# ESPTempMonitorSch.net
KiCad netlist of a schematic drawn in Altium Designer
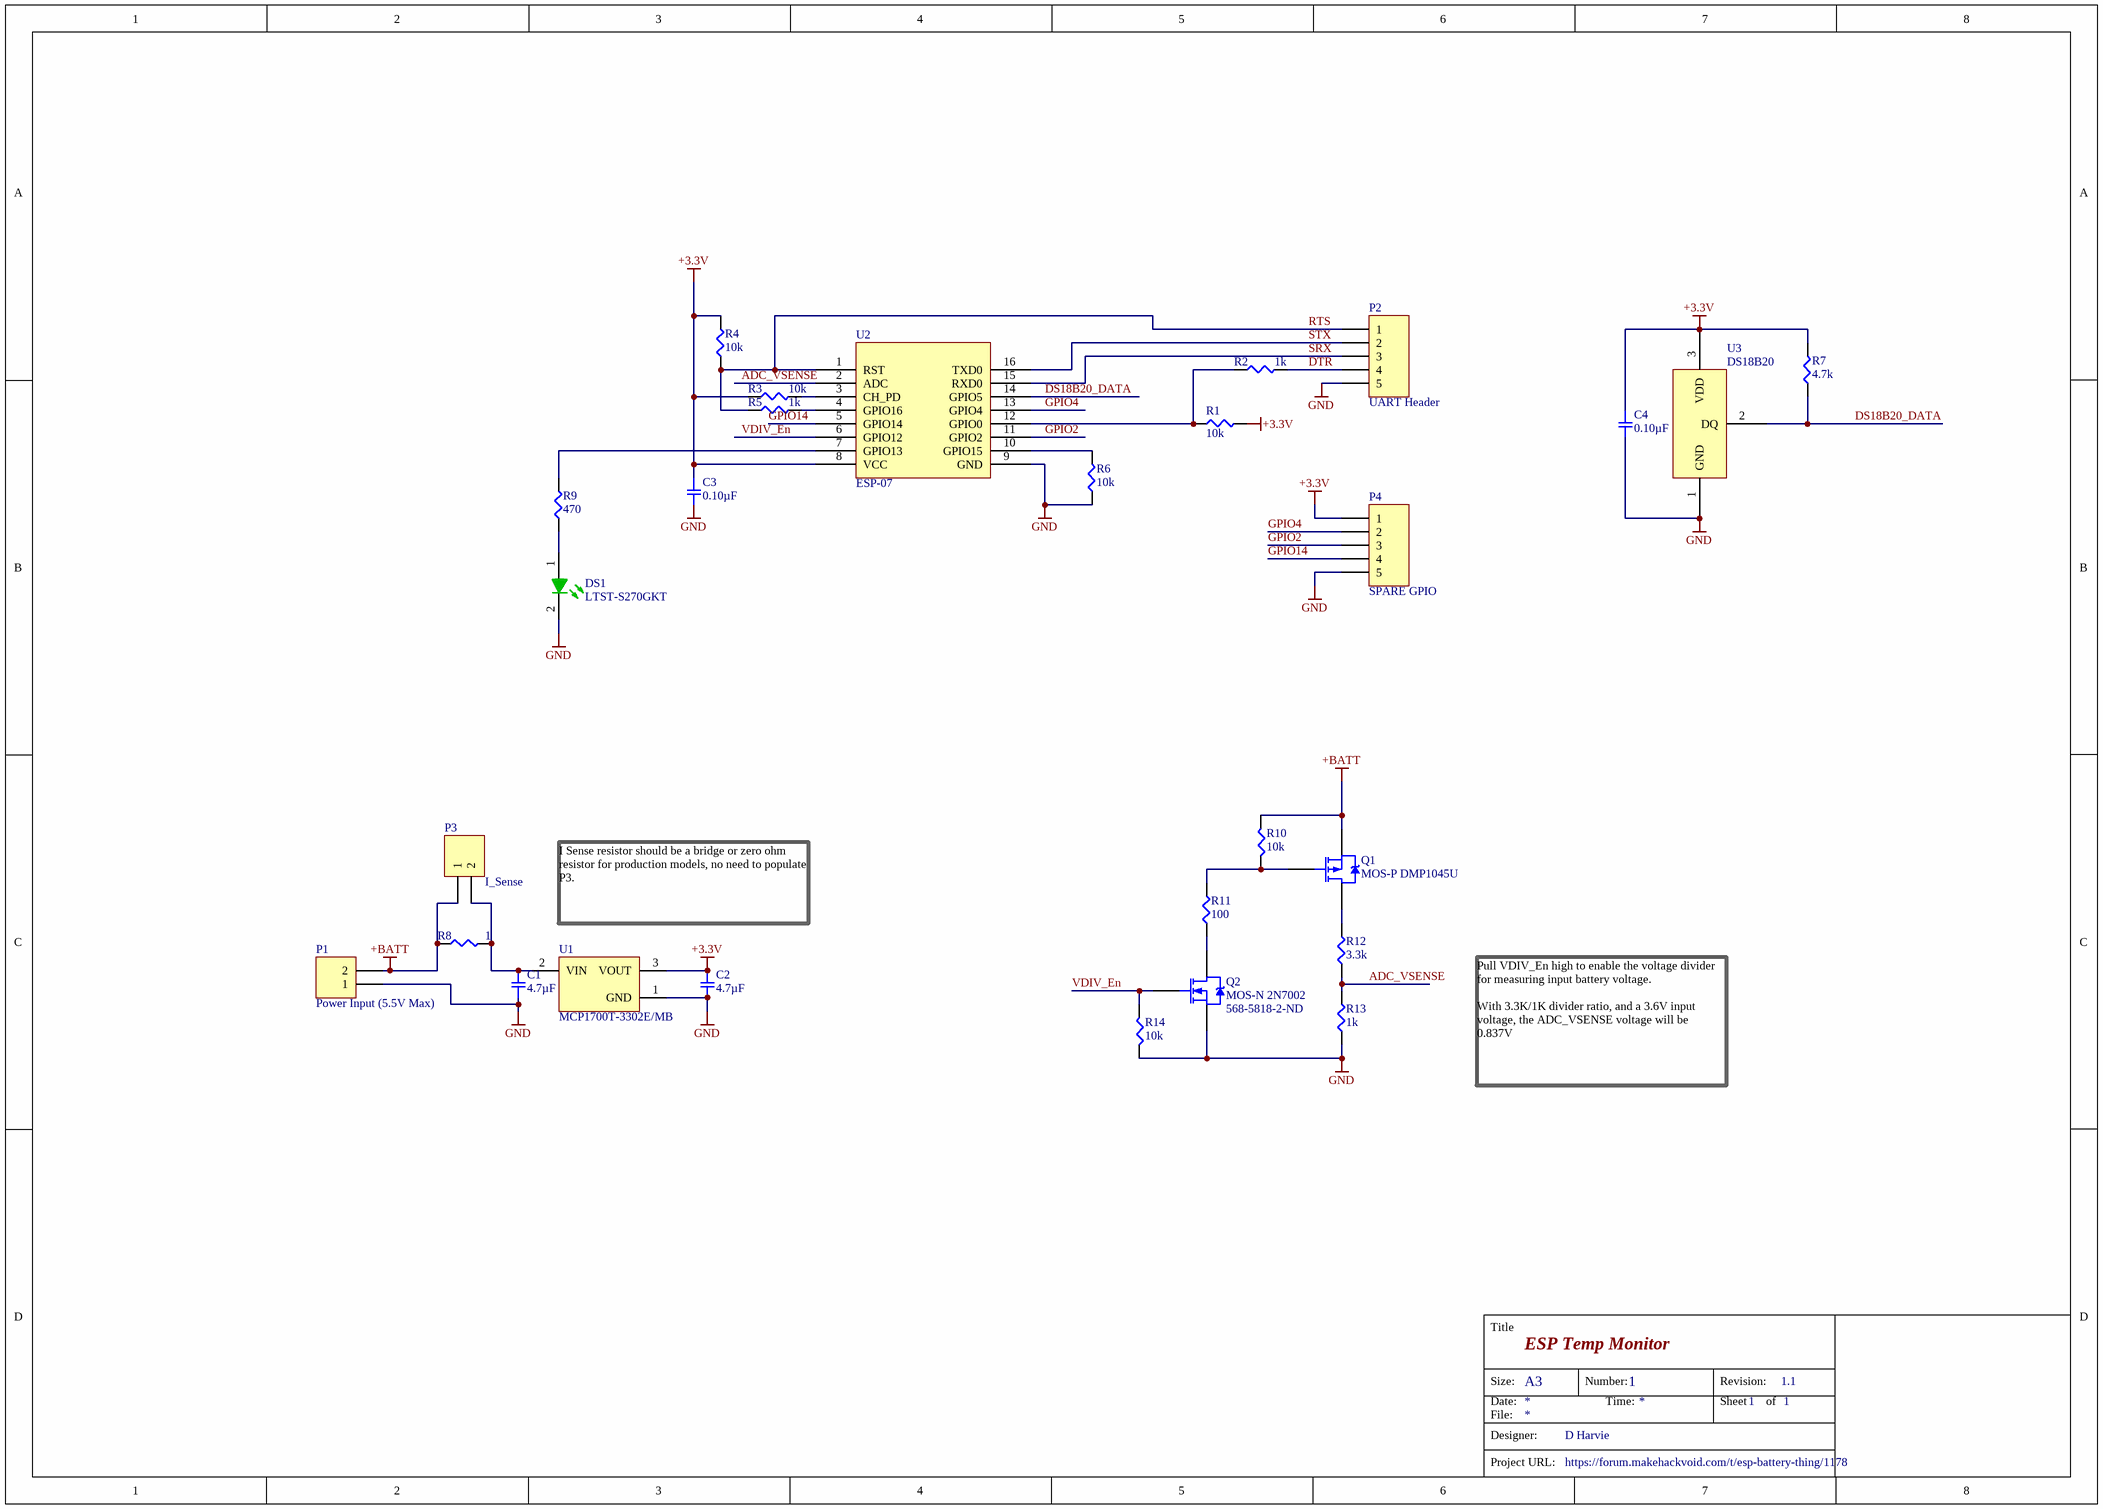
[diagram p0: ESPTempMonitorSch.SchDoc]

(export (version "E")
  (design (tool "Eeschema 10.0.6"))
  (components
    (comp (ref "C1")
      (value "4.7µF")
      (footprint "SMD-0805C")
      (description "CAP CER 4.7UF 16V X7R 0805")
      (fields
        (field (name "DIGI-KEY PART NUMBER") "490-10557-1-ND")
        (field (name "PART NUMBER") "GCJ21BR71C475KA01L")
      )
      (libsource (lib "capacitor_murata_0805") (part "GCJ21BR71C475KA01L"))
    )
    (comp (ref "C2")
      (value "4.7µF")
      (footprint "SMD-0805C")
      (description "CAP CER 4.7UF 16V X7R 0805")
      (fields
        (field (name "DIGI-KEY PART NUMBER") "490-10557-1-ND")
        (field (name "PART NUMBER") "GCJ21BR71C475KA01L")
      )
      (libsource (lib "capacitor_murata_0805") (part "GCJ21BR71C475KA01L"))
    )
    (comp (ref "C3")
      (value "0.10µF")
      (footprint "SMD-0603C")
      (description "CAP CER 0.1UF 16V X7R 0603")
      (fields
        (field (name "DIGI-KEY PART NUMBER") "490-5796-1-ND")
        (field (name "PART NUMBER") "GCJ188R71C104KA01D")
      )
      (libsource (lib "capacitor_murata_0603") (part "GCJ188R71C104KA01D"))
    )
    (comp (ref "C4")
      (value "0.10µF")
      (footprint "SMD-0603C")
      (description "CAP CER 0.1UF 16V X7R 0603")
      (fields
        (field (name "DIGI-KEY PART NUMBER") "490-5796-1-ND")
        (field (name "PART NUMBER") "GCJ188R71C104KA01D")
      )
      (libsource (lib "capacitor_murata_0603") (part "GCJ188R71C104KA01D"))
    )
    (comp (ref "DS1")
      (value "LTST-S270GKT")
      (footprint "KING-0603LED_GREEN_V")
      (description "Green 569nm LED Indication - Discrete 2.1V 0603")
      (libsource (lib "RepositLib") (part "SMD - LED - Discrete - 0603 - Green"))
    )
    (comp (ref "P1")
      (value "Power Input (5.5V Max)")
      (footprint "HDR1X2")
      (description "Power Input")
      (fields (field (name "PUBLISHER") "Altium Limited"))
      (libsource (lib "") (part "Header 2_1"))
    )
    (comp (ref "P2")
      (value "UART Header")
      (footprint "HDR1X5")
      (description "Header, 5-Pin")
      (fields (field (name "PUBLISHER") "Altium Limited"))
      (libsource (lib "Miscellaneous Connectors") (part "Header 5"))
    )
    (comp (ref "P3")
      (value "I_Sense")
      (footprint "HDR1X2")
      (description "Power Input")
      (fields (field (name "PUBLISHER") "Altium Limited"))
      (libsource (lib "Miscellaneous Connectors") (part "Header 2"))
    )
    (comp (ref "P4")
      (value "SPARE GPIO")
      (footprint "HDR1X5")
      (description "Header, 5-Pin")
      (fields (field (name "PUBLISHER") "Altium Limited"))
      (libsource (lib "Miscellaneous Connectors") (part "Header 5"))
    )
    (comp (ref "Q1")
      (value "MOS-P DMP1045U")
      (footprint "SOT-23B_N")
      (description "PMOS-DMP1045U")
      (fields (field (name "PUBLISHER") "Altium Limited"))
      (libsource (lib "MainLib") (part "MOS-P DMP1045U"))
    )
    (comp (ref "Q2")
      (value "MOS-N 2N7002")
      (footprint "SOT-23B_N")
      (description "N-MOSFET 2N7002 NXP")
      (fields
        (field (name "SUPPLIER PART NUMBER 1") "568-5818-2-ND")
        (field (name "PUBLISHER") "Altium Limited")
      )
      (libsource (lib "MainLib") (part "MOS-N 2N7002"))
    )
    (comp (ref "R1")
      (value "10k")
      (footprint "SMD-0603-RES")
      (description "RES SMD 10K OHM 5% 1/10W 0603")
      (fields (field (name "PART NUMBER") "ERJ-3GEYJ103V") (field (name "DIGI-KEY PART NUMBER") "P10KGCT-ND"))
      (libsource (lib "Panasonic_ERJ_0603") (part "ERJ-3GEYJ103V"))
    )
    (comp (ref "R2")
      (value "1k")
      (footprint "SMD-0603-RES")
      (description "RES SMD 1K OHM 1% 1/10W 0603")
      (fields
        (field (name "PART NUMBER") "ERJ-3EKF1001V")
        (field (name "DIGI-KEY PART NUMBER") "P1.00KHCT-ND")
      )
      (libsource (lib "Panasonic_ERJ_0603") (part "ERJ-3EKF1001V"))
    )
    (comp (ref "R3")
      (value "10k")
      (footprint "SMD-0603-RES")
      (description "RES SMD 10K OHM 5% 1/10W 0603")
      (fields (field (name "PART NUMBER") "ERJ-3GEYJ103V") (field (name "DIGI-KEY PART NUMBER") "P10KGCT-ND"))
      (libsource (lib "Panasonic_ERJ_0603") (part "ERJ-3GEYJ103V"))
    )
    (comp (ref "R4")
      (value "10k")
      (footprint "SMD-0603-RES")
      (description "RES SMD 10K OHM 5% 1/10W 0603")
      (fields (field (name "PART NUMBER") "ERJ-3GEYJ103V") (field (name "DIGI-KEY PART NUMBER") "P10KGCT-ND"))
      (libsource (lib "Panasonic_ERJ_0603") (part "ERJ-3GEYJ103V"))
    )
    (comp (ref "R5")
      (value "1k")
      (footprint "SMD-0603-RES")
      (description "RES SMD 1K OHM 1% 1/10W 0603")
      (fields
        (field (name "PART NUMBER") "ERJ-3EKF1001V")
        (field (name "DIGI-KEY PART NUMBER") "P1.00KHCT-ND")
      )
      (libsource (lib "Panasonic_ERJ_0603") (part "ERJ-3EKF1001V"))
    )
    (comp (ref "R6")
      (value "10k")
      (footprint "SMD-0603-RES")
      (description "RES SMD 10K OHM 5% 1/10W 0603")
      (fields (field (name "PART NUMBER") "ERJ-3GEYJ103V") (field (name "DIGI-KEY PART NUMBER") "P10KGCT-ND"))
      (libsource (lib "Panasonic_ERJ_0603") (part "ERJ-3GEYJ103V"))
    )
    (comp (ref "R7")
      (value "4.7k")
      (footprint "SMD-0603-RES")
      (description "RES SMD 4.7K OHM 5% 1/10W 0603")
      (fields
        (field (name "PART NUMBER") "ERJ-3GEYJ472V")
        (field (name "DIGI-KEY PART NUMBER") "P4.7KGCT-ND")
      )
      (libsource (lib "Panasonic_ERJ_0603") (part "ERJ-3GEYJ472V"))
    )
    (comp (ref "R8")
      (value "1")
      (footprint "SMD-0603-RES")
      (description "RES SMD 1 OHM 1% 1/4W 0603")
      (fields (field (name "PART NUMBER") "ERJ-3BQF1R0V") (field (name "DIGI-KEY PART NUMBER") "P17371CT-ND"))
      (libsource (lib "Panasonic_ERJ_0603") (part "ERJ-3BQF1R0V"))
    )
    (comp (ref "R9")
      (value "470")
      (footprint "SMD-0603-RES")
      (description "RES SMD 470 OHM 5% 1/10W 0603")
      (fields (field (name "PART NUMBER") "ERJ-3GEYJ471V") (field (name "DIGI-KEY PART NUMBER") "P470GCT-ND"))
      (libsource (lib "Panasonic_ERJ_0603") (part "ERJ-3GEYJ471V"))
    )
    (comp (ref "R10")
      (value "10k")
      (footprint "SMD-0603-RES")
      (description "RES SMD 10K OHM 5% 1/10W 0603")
      (fields (field (name "PART NUMBER") "ERJ-3GEYJ103V") (field (name "DIGI-KEY PART NUMBER") "P10KGCT-ND"))
      (libsource (lib "Panasonic_ERJ_0603") (part "ERJ-3GEYJ103V"))
    )
    (comp (ref "R11")
      (value "100")
      (footprint "SMD-0603-RES")
      (description "RES SMD 100 OHM 1% 1/10W 0603")
      (fields (field (name "PART NUMBER") "ERJ-3EKF1000V") (field (name "DIGI-KEY PART NUMBER") "P100HCT-ND"))
      (libsource (lib "Panasonic_ERJ_0603") (part "ERJ-3EKF1000V"))
    )
    (comp (ref "R12")
      (value "3.3k")
      (footprint "SMD-0603-RES")
      (description "RES SMD 3.3K OHM 1% 1/10W 0603")
      (fields
        (field (name "PART NUMBER") "ERJ-3EKF3301V")
        (field (name "DIGI-KEY PART NUMBER") "P3.30KHCT-ND")
      )
      (libsource (lib "Panasonic_ERJ_0603") (part "ERJ-3EKF3301V"))
    )
    (comp (ref "R13")
      (value "1k")
      (footprint "SMD-0603-RES")
      (description "RES SMD 1K OHM 1% 1/10W 0603")
      (fields
        (field (name "PART NUMBER") "ERJ-3EKF1001V")
        (field (name "DIGI-KEY PART NUMBER") "P1.00KHCT-ND")
      )
      (libsource (lib "Panasonic_ERJ_0603") (part "ERJ-3EKF1001V"))
    )
    (comp (ref "R14")
      (value "10k")
      (footprint "SMD-0603-RES")
      (description "RES SMD 10K OHM 5% 1/10W 0603")
      (fields (field (name "PART NUMBER") "ERJ-3GEYJ103V") (field (name "DIGI-KEY PART NUMBER") "P10KGCT-ND"))
      (libsource (lib "Panasonic_ERJ_0603") (part "ERJ-3GEYJ103V"))
    )
    (comp (ref "U1")
      (value "MCP1700T-3302E/MB")
      (footprint "SOT-89-MB3_M")
      (description "Low Quiescent Current LDO, 3-Pin SOT-89, Extended Temperature, Tape and Reel")
      (libsource (lib "Altium Content Vault") (part "PM-LINEREG-MCP1700-IL3A"))
    )
    (comp (ref "U2")
      (value "ESP-07")
      (footprint "ESP-07")
      (description "ESP8266 ESP-07 Module")
      (libsource (lib "ESPTempMonitor") (part "ESP-07"))
    )
    (comp (ref "U3")
      (value "DS18B20")
      (footprint "DS18B20-SIDE")
      (description "SENSOR TEMPERATURE 1-WIRE TO92-3")
      (libsource (lib "ESPTempMonitor") (part "DS18B20"))
    )
  )
  (nets
    (net (code "1") (name "+3.3V") (class "Default")
      (node (ref "C2") (pin "1") (pinfunction "1_1") (pintype "passive"))
      (node (ref "C3") (pin "1") (pinfunction "1_1") (pintype "passive"))
      (node (ref "C4") (pin "1") (pinfunction "1_1") (pintype "passive"))
      (node (ref "P4") (pin "1") (pinfunction "1_1") (pintype "passive"))
      (node (ref "R1") (pin "2") (pinfunction "2_2") (pintype "passive"))
      (node (ref "R3") (pin "1") (pinfunction "1_1") (pintype "passive"))
      (node (ref "R4") (pin "2") (pinfunction "2_2") (pintype "passive"))
      (node (ref "R7") (pin "2") (pinfunction "2_2") (pintype "passive"))
      (node (ref "U1") (pin "3") (pinfunction "VOUT_3") (pintype "power_in"))
      (node (ref "U2") (pin "8") (pinfunction "VCC_8") (pintype "passive"))
      (node (ref "U3") (pin "3") (pinfunction "VDD_3") (pintype "passive"))
    )
    (net (code "2") (name "+BATT") (class "Default")
      (node (ref "P1") (pin "2") (pinfunction "2_2") (pintype "passive"))
      (node (ref "P3") (pin "1") (pinfunction "1_1") (pintype "passive"))
      (node (ref "Q1") (pin "2") (pinfunction "S_2") (pintype "passive"))
      (node (ref "R10") (pin "2") (pinfunction "2_2") (pintype "passive"))
      (node (ref "R8") (pin "1") (pinfunction "1_1") (pintype "passive"))
    )
    (net (code "3") (name "/ADC_VSENSE") (class "Default")
      (node (ref "R12") (pin "1") (pinfunction "1_1") (pintype "passive"))
      (node (ref "R13") (pin "2") (pinfunction "2_2") (pintype "passive"))
      (node (ref "U2") (pin "2") (pinfunction "ADC_2") (pintype "passive"))
    )
    (net (code "4") (name "/DS18B20_DATA") (class "Default")
      (node (ref "R7") (pin "1") (pinfunction "1_1") (pintype "passive"))
      (node (ref "U2") (pin "14") (pinfunction "GPIO5_14") (pintype "passive"))
      (node (ref "U3") (pin "2") (pinfunction "DQ_2") (pintype "passive"))
    )
    (net (code "5") (name "/DTR") (class "Default")
      (node (ref "P2") (pin "4") (pinfunction "4_4") (pintype "passive"))
      (node (ref "R2") (pin "2") (pinfunction "2_2") (pintype "passive"))
    )
    (net (code "6") (name "/GPIO2") (class "Default")
      (node (ref "P4") (pin "3") (pinfunction "3_3") (pintype "passive"))
      (node (ref "U2") (pin "11") (pinfunction "GPIO2_11") (pintype "passive"))
    )
    (net (code "7") (name "/GPIO4") (class "Default")
      (node (ref "P4") (pin "2") (pinfunction "2_2") (pintype "passive"))
      (node (ref "U2") (pin "13") (pinfunction "GPIO4_13") (pintype "passive"))
    )
    (net (code "8") (name "/GPIO14") (class "Default")
      (node (ref "P4") (pin "4") (pinfunction "4_4") (pintype "passive"))
      (node (ref "U2") (pin "5") (pinfunction "GPIO14_5") (pintype "passive"))
    )
    (net (code "9") (name "/RTS") (class "Default")
      (node (ref "P2") (pin "1") (pinfunction "1_1") (pintype "passive"))
      (node (ref "R4") (pin "1") (pinfunction "1_1") (pintype "passive"))
      (node (ref "R5") (pin "1") (pinfunction "1_1") (pintype "passive"))
      (node (ref "U2") (pin "1") (pinfunction "RST_1") (pintype "passive"))
    )
    (net (code "10") (name "/SRX") (class "Default")
      (node (ref "P2") (pin "3") (pinfunction "3_3") (pintype "passive"))
      (node (ref "U2") (pin "15") (pinfunction "RXD0_15") (pintype "passive"))
    )
    (net (code "11") (name "/STX") (class "Default")
      (node (ref "P2") (pin "2") (pinfunction "2_2") (pintype "passive"))
      (node (ref "U2") (pin "16") (pinfunction "TXD0_16") (pintype "passive"))
    )
    (net (code "12") (name "/VDIV_En") (class "Default")
      (node (ref "Q2") (pin "1") (pinfunction "G_1") (pintype "passive"))
      (node (ref "R14") (pin "2") (pinfunction "2_2") (pintype "passive"))
      (node (ref "U2") (pin "6") (pinfunction "GPIO12_6") (pintype "passive"))
    )
    (net (code "13") (name "GND") (class "Default")
      (node (ref "C1") (pin "2") (pinfunction "2_2") (pintype "passive"))
      (node (ref "C2") (pin "2") (pinfunction "2_2") (pintype "passive"))
      (node (ref "C3") (pin "2") (pinfunction "2_2") (pintype "passive"))
      (node (ref "C4") (pin "2") (pinfunction "2_2") (pintype "passive"))
      (node (ref "DS1") (pin "2") (pinfunction "K_2") (pintype "passive"))
      (node (ref "P1") (pin "1") (pinfunction "1_1") (pintype "passive"))
      (node (ref "P2") (pin "5") (pinfunction "5_5") (pintype "passive"))
      (node (ref "P4") (pin "5") (pinfunction "5_5") (pintype "passive"))
      (node (ref "Q2") (pin "2") (pinfunction "S_2") (pintype "passive"))
      (node (ref "R13") (pin "1") (pinfunction "1_1") (pintype "passive"))
      (node (ref "R14") (pin "1") (pinfunction "1_1") (pintype "passive"))
      (node (ref "R6") (pin "1") (pinfunction "1_1") (pintype "passive"))
      (node (ref "U1") (pin "1") (pinfunction "GND_1") (pintype "power_in"))
      (node (ref "U2") (pin "9") (pinfunction "GND_9") (pintype "passive"))
      (node (ref "U3") (pin "1") (pinfunction "GND_1") (pintype "passive"))
    )
    (net (code "14") (name "Net-(DS1-A)") (class "Default")
      (node (ref "DS1") (pin "1") (pinfunction "A_1") (pintype "passive"))
      (node (ref "R9") (pin "1") (pinfunction "1_1") (pintype "passive"))
    )
    (net (code "15") (name "Net-(Q1-D)") (class "Default")
      (node (ref "Q1") (pin "3") (pinfunction "D_3") (pintype "passive"))
      (node (ref "R12") (pin "2") (pinfunction "2_2") (pintype "passive"))
    )
    (net (code "16") (name "Net-(Q1-G)") (class "Default")
      (node (ref "Q1") (pin "1") (pinfunction "G_1") (pintype "passive"))
      (node (ref "R10") (pin "1") (pinfunction "1_1") (pintype "passive"))
      (node (ref "R11") (pin "2") (pinfunction "2_2") (pintype "passive"))
    )
    (net (code "17") (name "Net-(Q2-D)") (class "Default")
      (node (ref "Q2") (pin "3") (pinfunction "D_3") (pintype "passive"))
      (node (ref "R11") (pin "1") (pinfunction "1_1") (pintype "passive"))
    )
    (net (code "18") (name "Net-(U1-VIN)") (class "Default")
      (node (ref "C1") (pin "1") (pinfunction "1_1") (pintype "passive"))
      (node (ref "P3") (pin "2") (pinfunction "2_2") (pintype "passive"))
      (node (ref "R8") (pin "2") (pinfunction "2_2") (pintype "passive"))
      (node (ref "U1") (pin "2") (pinfunction "VIN_2") (pintype "power_in"))
    )
    (net (code "19") (name "Net-(U2-CH_PD)") (class "Default")
      (node (ref "R3") (pin "2") (pinfunction "2_2") (pintype "passive"))
      (node (ref "U2") (pin "3") (pinfunction "CH_PD_3") (pintype "passive"))
    )
    (net (code "20") (name "Net-(U2-GPIO0)") (class "Default")
      (node (ref "R1") (pin "1") (pinfunction "1_1") (pintype "passive"))
      (node (ref "R2") (pin "1") (pinfunction "1_1") (pintype "passive"))
      (node (ref "U2") (pin "12") (pinfunction "GPIO0_12") (pintype "passive"))
    )
    (net (code "21") (name "Net-(U2-GPIO13)") (class "Default")
      (node (ref "R9") (pin "2") (pinfunction "2_2") (pintype "passive"))
      (node (ref "U2") (pin "7") (pinfunction "GPIO13_7") (pintype "passive"))
    )
    (net (code "22") (name "Net-(U2-GPIO15)") (class "Default")
      (node (ref "R6") (pin "2") (pinfunction "2_2") (pintype "passive"))
      (node (ref "U2") (pin "10") (pinfunction "GPIO15_10") (pintype "passive"))
    )
    (net (code "23") (name "Net-(U2-GPIO16)") (class "Default")
      (node (ref "R5") (pin "2") (pinfunction "2_2") (pintype "passive"))
      (node (ref "U2") (pin "4") (pinfunction "GPIO16_4") (pintype "passive"))
    )
  )
)
